# sceme1_0.net
KiCad netlist of a schematic drawn in EAGLE
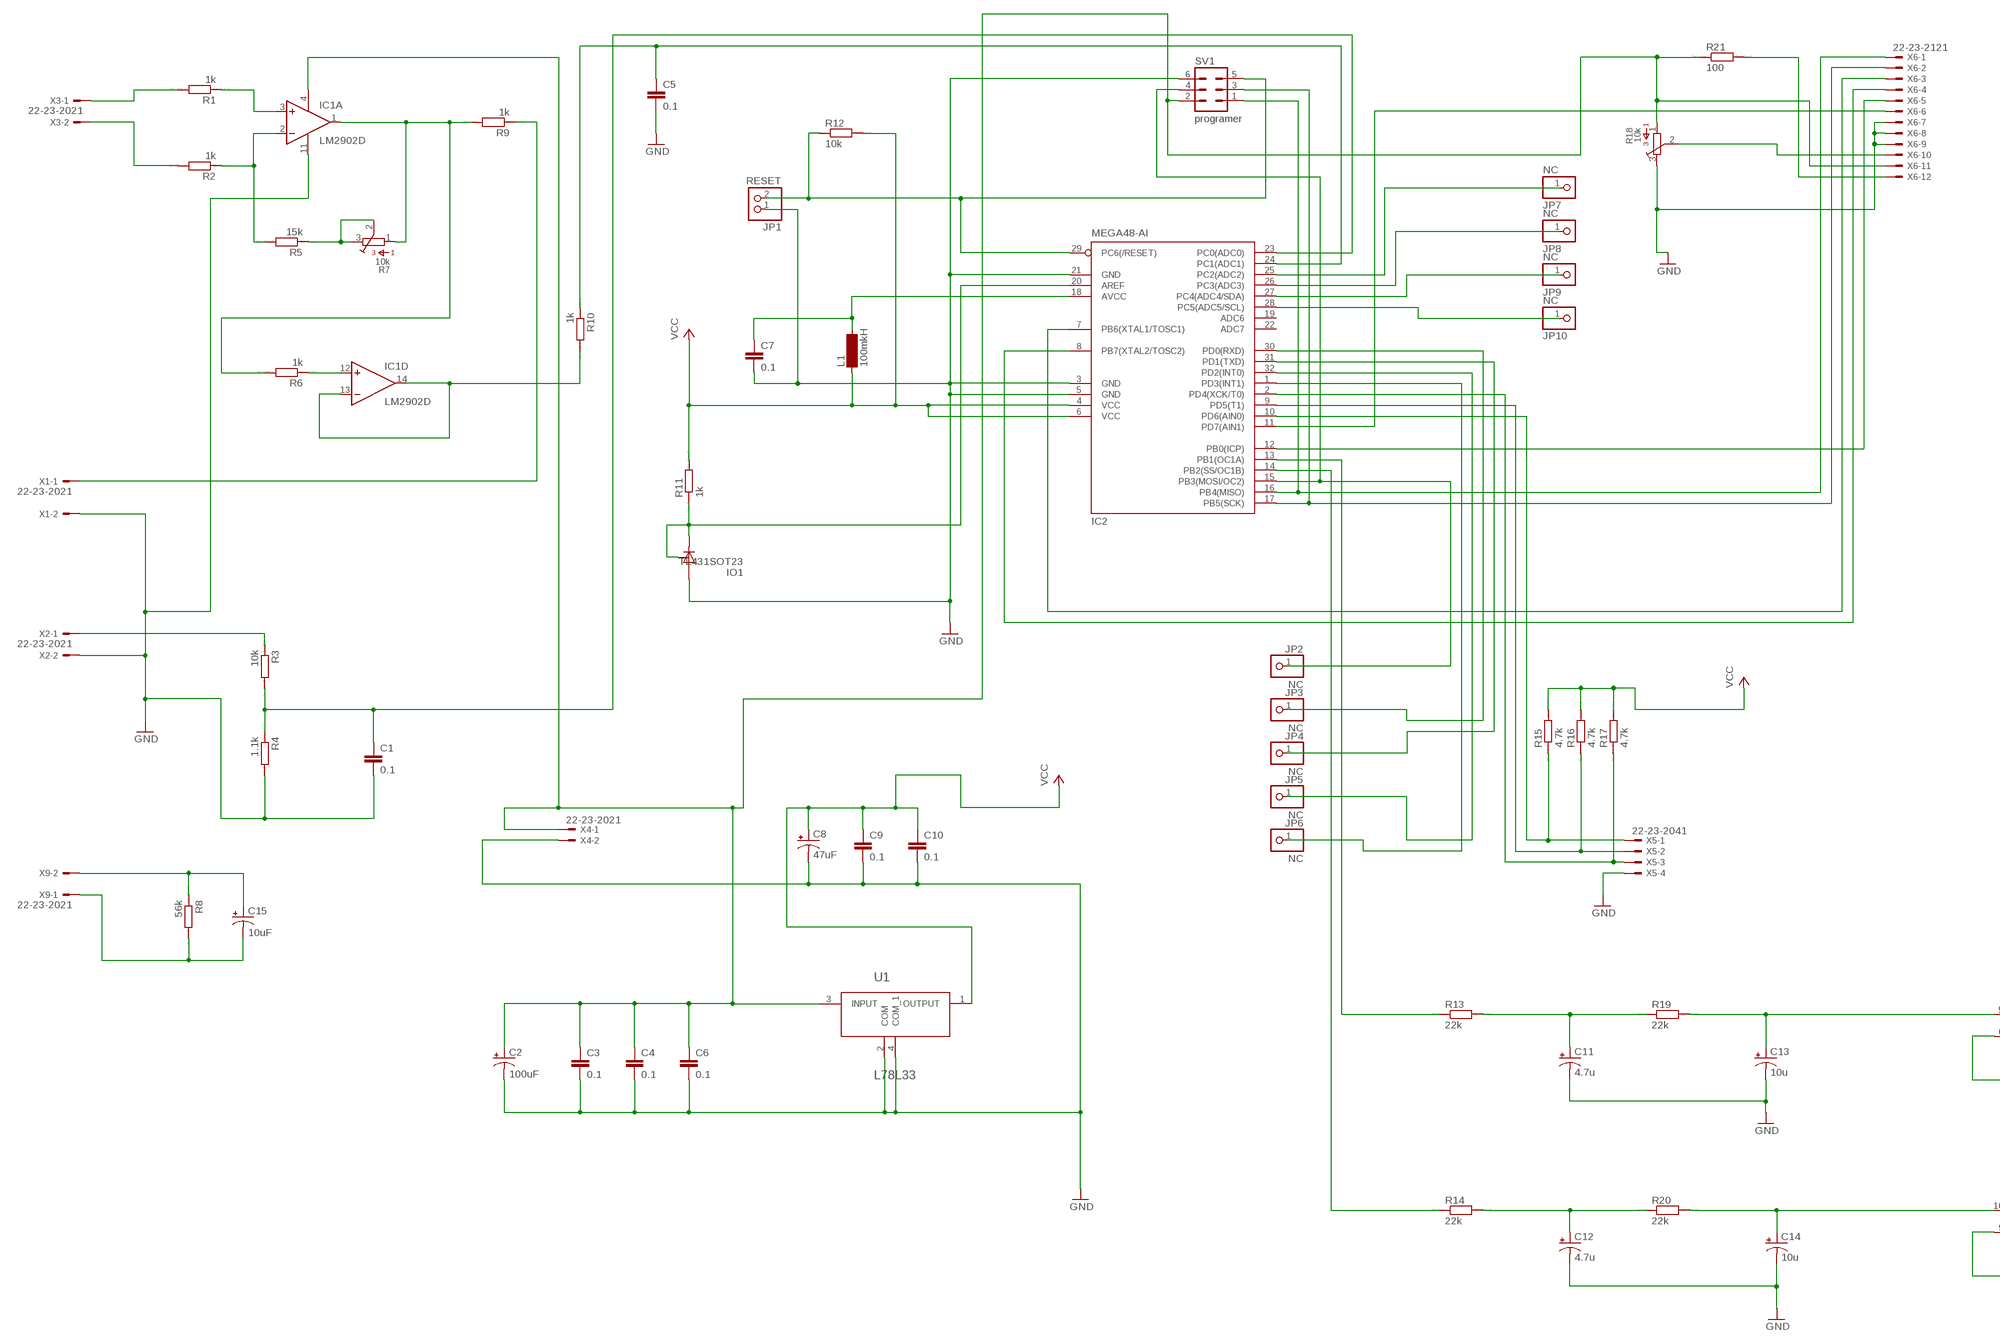
[diagram p0: schematic, sheet 1, part 1 of 2]
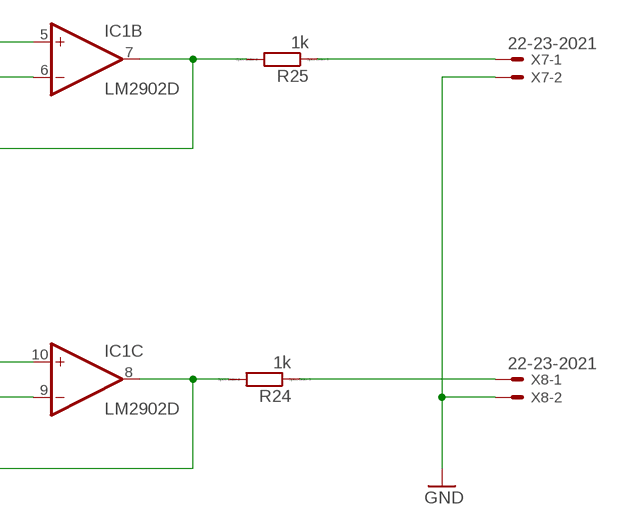
[diagram p1: schematic, sheet 1, part 2 of 2]

(export (version "E")
  (design (tool "Eeschema 10.0.6"))
  (components
    (comp (ref "C1")
      (value "0.1")
      (footprint "eagle-import:C0805")
      (libsource (lib "eagle-import") (part "C-EUC0805"))
    )
    (comp (ref "C2")
      (value "100uF")
      (footprint "eagle-import:E2,5-5")
      (libsource (lib "eagle-import") (part "CPOL-USE2.5-5"))
    )
    (comp (ref "C3")
      (value "0.1")
      (footprint "eagle-import:C0805")
      (libsource (lib "eagle-import") (part "C-EUC0805"))
    )
    (comp (ref "C4")
      (value "0.1")
      (footprint "eagle-import:C0805")
      (libsource (lib "eagle-import") (part "C-EUC0805"))
    )
    (comp (ref "C5")
      (value "0.1")
      (footprint "eagle-import:C0805")
      (libsource (lib "eagle-import") (part "C-EUC0805"))
    )
    (comp (ref "C6")
      (value "0.1")
      (footprint "eagle-import:C0805")
      (libsource (lib "eagle-import") (part "C-EUC0805"))
    )
    (comp (ref "C7")
      (value "0.1")
      (footprint "eagle-import:C0805")
      (libsource (lib "eagle-import") (part "C-EUC0805"))
    )
    (comp (ref "C8")
      (value "47uF")
      (footprint "eagle-import:E2,5-5")
      (libsource (lib "eagle-import") (part "CPOL-USE2.5-5"))
    )
    (comp (ref "C9")
      (value "0.1")
      (footprint "eagle-import:C0805")
      (libsource (lib "eagle-import") (part "C-EUC0805"))
    )
    (comp (ref "C10")
      (value "0.1")
      (footprint "eagle-import:C0805")
      (libsource (lib "eagle-import") (part "C-EUC0805"))
    )
    (comp (ref "C11")
      (value "4.7u")
      (footprint "eagle-import:E2,5-5")
      (libsource (lib "eagle-import") (part "CPOL-USE2.5-5"))
    )
    (comp (ref "C12")
      (value "4.7u")
      (footprint "eagle-import:E2,5-5")
      (libsource (lib "eagle-import") (part "CPOL-USE2.5-5"))
    )
    (comp (ref "C13")
      (value "10u")
      (footprint "eagle-import:E2,5-5")
      (libsource (lib "eagle-import") (part "CPOL-USE2.5-5"))
    )
    (comp (ref "C14")
      (value "10u")
      (footprint "eagle-import:E2,5-5")
      (libsource (lib "eagle-import") (part "CPOL-USE2.5-5"))
    )
    (comp (ref "C15")
      (value "10uF")
      (footprint "eagle-import:E2,5-5")
      (libsource (lib "eagle-import") (part "CPOL-USE2.5-5"))
    )
    (comp (ref "IC1")
      (value "LM2902D")
      (footprint "eagle-import:SO14")
      (libsource (lib "eagle-import") (part "LM2902D"))
    )
    (comp (ref "IC2")
      (value "MEGA48-AI")
      (footprint "eagle-import:TQFP32-08")
      (fields (field (name "MPN") "ATMEGA8-16AU"))
      (libsource (lib "eagle-import") (part "MEGA8-AI"))
    )
    (comp (ref "IO1")
      (value "TL431SOT23")
      (footprint "eagle-import:SOT23")
      (fields (field (name "MPN") "TL431BFDT"))
      (libsource (lib "eagle-import") (part "TL431SOT23"))
    )
    (comp (ref "JP1")
      (value "RESET")
      (footprint "eagle-import:1X02")
      (libsource (lib "eagle-import") (part "PINHD-1X2"))
    )
    (comp (ref "JP2")
      (value "NC")
      (footprint "eagle-import:1X01")
      (libsource (lib "eagle-import") (part "PINHD-1X1"))
    )
    (comp (ref "JP3")
      (value "NC")
      (footprint "eagle-import:1X01")
      (libsource (lib "eagle-import") (part "PINHD-1X1"))
    )
    (comp (ref "JP4")
      (value "NC")
      (footprint "eagle-import:1X01")
      (libsource (lib "eagle-import") (part "PINHD-1X1"))
    )
    (comp (ref "JP5")
      (value "NC")
      (footprint "eagle-import:1X01")
      (libsource (lib "eagle-import") (part "PINHD-1X1"))
    )
    (comp (ref "JP6")
      (value "NC")
      (footprint "eagle-import:1X01")
      (libsource (lib "eagle-import") (part "PINHD-1X1"))
    )
    (comp (ref "JP7")
      (value "NC")
      (footprint "eagle-import:1X01")
      (libsource (lib "eagle-import") (part "PINHD-1X1"))
    )
    (comp (ref "JP8")
      (value "NC")
      (footprint "eagle-import:1X01")
      (libsource (lib "eagle-import") (part "PINHD-1X1"))
    )
    (comp (ref "JP9")
      (value "NC")
      (footprint "eagle-import:1X01")
      (libsource (lib "eagle-import") (part "PINHD-1X1"))
    )
    (comp (ref "JP10")
      (value "NC")
      (footprint "eagle-import:1X01")
      (libsource (lib "eagle-import") (part "PINHD-1X1"))
    )
    (comp (ref "L1")
      (value "100mkH")
      (footprint "eagle-import:SM-1206")
      (libsource (lib "eagle-import") (part "SM-1206"))
    )
    (comp (ref "R1")
      (value "1k")
      (footprint "eagle-import:R0805")
      (libsource (lib "eagle-import") (part "R"))
    )
    (comp (ref "R2")
      (value "1k")
      (footprint "eagle-import:R0805")
      (libsource (lib "eagle-import") (part "R"))
    )
    (comp (ref "R3")
      (value "10k")
      (footprint "eagle-import:R0805")
      (libsource (lib "eagle-import") (part "R"))
    )
    (comp (ref "R4")
      (value "1.1k")
      (footprint "eagle-import:R0805")
      (libsource (lib "eagle-import") (part "R"))
    )
    (comp (ref "R5")
      (value "15k")
      (footprint "eagle-import:R0805")
      (libsource (lib "eagle-import") (part "R"))
    )
    (comp (ref "R6")
      (value "1k")
      (footprint "eagle-import:R0805")
      (libsource (lib "eagle-import") (part "R"))
    )
    (comp (ref "R7")
      (value "10k")
      (footprint "eagle-import:3362P")
      (libsource (lib "eagle-import") (part "3362P"))
    )
    (comp (ref "R8")
      (value "56k")
      (footprint "eagle-import:R0805")
      (libsource (lib "eagle-import") (part "R"))
    )
    (comp (ref "R9")
      (value "1k")
      (footprint "eagle-import:R0805")
      (libsource (lib "eagle-import") (part "R"))
    )
    (comp (ref "R10")
      (value "1k")
      (footprint "eagle-import:R0805")
      (libsource (lib "eagle-import") (part "R"))
    )
    (comp (ref "R11")
      (value "1k")
      (footprint "eagle-import:R0805")
      (libsource (lib "eagle-import") (part "R"))
    )
    (comp (ref "R12")
      (value "10k")
      (footprint "eagle-import:R0805")
      (libsource (lib "eagle-import") (part "R"))
    )
    (comp (ref "R13")
      (value "22k")
      (footprint "eagle-import:R0805")
      (libsource (lib "eagle-import") (part "R"))
    )
    (comp (ref "R14")
      (value "22k")
      (footprint "eagle-import:R0805")
      (libsource (lib "eagle-import") (part "R"))
    )
    (comp (ref "R15")
      (value "4.7k")
      (footprint "eagle-import:R0805")
      (libsource (lib "eagle-import") (part "R"))
    )
    (comp (ref "R16")
      (value "4.7k")
      (footprint "eagle-import:R0805")
      (libsource (lib "eagle-import") (part "R"))
    )
    (comp (ref "R17")
      (value "4.7k")
      (footprint "eagle-import:R0805")
      (libsource (lib "eagle-import") (part "R"))
    )
    (comp (ref "R18")
      (value "10k")
      (footprint "eagle-import:3362P")
      (libsource (lib "eagle-import") (part "3362P"))
    )
    (comp (ref "R19")
      (value "22k")
      (footprint "eagle-import:R0805")
      (libsource (lib "eagle-import") (part "R"))
    )
    (comp (ref "R20")
      (value "22k")
      (footprint "eagle-import:R0805")
      (libsource (lib "eagle-import") (part "R"))
    )
    (comp (ref "R21")
      (value "100")
      (footprint "eagle-import:R0805")
      (libsource (lib "eagle-import") (part "R"))
    )
    (comp (ref "R24")
      (value "1k")
      (footprint "eagle-import:R0805")
      (libsource (lib "eagle-import") (part "R"))
    )
    (comp (ref "R25")
      (value "1k")
      (footprint "eagle-import:R0805")
      (libsource (lib "eagle-import") (part "R"))
    )
    (comp (ref "SV1")
      (value "programer")
      (footprint "eagle-import:ML6")
      (libsource (lib "eagle-import") (part "ML6"))
    )
    (comp (ref "U1")
      (value "L78L33")
      (footprint "eagle-import:SOT150P400X160-4N")
      (fields (field (name "MPN") "UA78L05CPK"))
      (libsource (lib "eagle-import") (part "UA78L05CPK"))
    )
    (comp (ref "X1")
      (value "22-23-2021")
      (footprint "eagle-import:22-23-2021")
      (fields (field (name "MF") "MOLEX"))
      (libsource (lib "eagle-import") (part "22-23-2021"))
    )
    (comp (ref "X2")
      (value "22-23-2021")
      (footprint "eagle-import:22-23-2021")
      (fields (field (name "MF") "MOLEX"))
      (libsource (lib "eagle-import") (part "22-23-2021"))
    )
    (comp (ref "X3")
      (value "22-23-2021")
      (footprint "eagle-import:22-23-2021")
      (fields (field (name "MF") "MOLEX"))
      (libsource (lib "eagle-import") (part "22-23-2021"))
    )
    (comp (ref "X4")
      (value "22-23-2021")
      (footprint "eagle-import:22-23-2021")
      (fields (field (name "MF") "MOLEX"))
      (libsource (lib "eagle-import") (part "22-23-2021"))
    )
    (comp (ref "X5")
      (value "22-23-2041")
      (footprint "eagle-import:22-23-2041")
      (fields (field (name "MF") "MOLEX"))
      (libsource (lib "eagle-import") (part "22-23-2041"))
    )
    (comp (ref "X6")
      (value "22-23-2121")
      (footprint "eagle-import:22-23-2121")
      (fields (field (name "MF") "MOLEX"))
      (libsource (lib "eagle-import") (part "22-23-2121"))
    )
    (comp (ref "X7")
      (value "22-23-2021")
      (footprint "eagle-import:22-23-2021")
      (fields (field (name "MF") "MOLEX"))
      (libsource (lib "eagle-import") (part "22-23-2021"))
    )
    (comp (ref "X8")
      (value "22-23-2021")
      (footprint "eagle-import:22-23-2021")
      (fields (field (name "MF") "MOLEX"))
      (libsource (lib "eagle-import") (part "22-23-2021"))
    )
    (comp (ref "X9")
      (value "22-23-2021")
      (footprint "eagle-import:22-23-2021")
      (fields (field (name "MF") "MOLEX"))
      (libsource (lib "eagle-import") (part "22-23-2021"))
    )
  )
  (nets
    (net (code "1") (name "GND") (class "Default")
      (node (ref "C1") (pin "2") (pinfunction "2_2") (pintype "passive"))
      (node (ref "C10") (pin "2") (pinfunction "2_2") (pintype "passive"))
      (node (ref "C11") (pin "-") (pinfunction "-_-") (pintype "passive"))
      (node (ref "C12") (pin "-") (pinfunction "-_-") (pintype "passive"))
      (node (ref "C13") (pin "-") (pinfunction "-_-") (pintype "passive"))
      (node (ref "C14") (pin "-") (pinfunction "-_-") (pintype "passive"))
      (node (ref "C2") (pin "-") (pinfunction "-_-") (pintype "passive"))
      (node (ref "C3") (pin "2") (pinfunction "2_2") (pintype "passive"))
      (node (ref "C4") (pin "2") (pinfunction "2_2") (pintype "passive"))
      (node (ref "C5") (pin "2") (pinfunction "2_2") (pintype "passive"))
      (node (ref "C6") (pin "2") (pinfunction "2_2") (pintype "passive"))
      (node (ref "C7") (pin "2") (pinfunction "2_2") (pintype "passive"))
      (node (ref "C8") (pin "-") (pinfunction "-_-") (pintype "passive"))
      (node (ref "C9") (pin "2") (pinfunction "2_2") (pintype "passive"))
      (node (ref "IC1") (pin "11") (pinfunction "V-_11") (pintype "power_in"))
      (node (ref "IC2") (pin "21") (pinfunction "GND_21") (pintype "power_in"))
      (node (ref "IC2") (pin "3") (pinfunction "GND_3") (pintype "power_in"))
      (node (ref "IC2") (pin "5") (pinfunction "GND_5") (pintype "power_in"))
      (node (ref "IO1") (pin "3") (pinfunction "A_3") (pintype "bidirectional"))
      (node (ref "JP1") (pin "1") (pinfunction "1_1") (pintype "passive"))
      (node (ref "R18") (pin "3") (pinfunction "3_3") (pintype "passive"))
      (node (ref "R4") (pin "2") (pinfunction "2_2") (pintype "passive"))
      (node (ref "SV1") (pin "6") (pinfunction "6_6") (pintype "passive"))
      (node (ref "U1") (pin "2") (pinfunction "COM_2") (pintype "power_in"))
      (node (ref "U1") (pin "4") (pinfunction "COM_1_4") (pintype "power_in"))
      (node (ref "X1") (pin "2") (pinfunction "S_2") (pintype "passive"))
      (node (ref "X2") (pin "2") (pinfunction "S_2") (pintype "passive"))
      (node (ref "X4") (pin "2") (pinfunction "S_2") (pintype "passive"))
      (node (ref "X5") (pin "4") (pinfunction "S_4") (pintype "passive"))
      (node (ref "X6") (pin "7") (pinfunction "S_7") (pintype "passive"))
      (node (ref "X6") (pin "8") (pinfunction "S_8") (pintype "passive"))
      (node (ref "X6") (pin "9") (pinfunction "S_9") (pintype "passive"))
      (node (ref "X7") (pin "2") (pinfunction "S_2") (pintype "passive"))
      (node (ref "X8") (pin "2") (pinfunction "S_2") (pintype "passive"))
    )
    (net (code "2") (name "Net-(C11-Pad+)") (class "Default")
      (node (ref "C11") (pin "+") (pinfunction "+_+") (pintype "passive"))
      (node (ref "R13") (pin "2") (pinfunction "2_2") (pintype "passive"))
      (node (ref "R19") (pin "1") (pinfunction "1_1") (pintype "passive"))
    )
    (net (code "3") (name "Net-(C12-Pad+)") (class "Default")
      (node (ref "C12") (pin "+") (pinfunction "+_+") (pintype "passive"))
      (node (ref "R14") (pin "2") (pinfunction "2_2") (pintype "passive"))
      (node (ref "R20") (pin "1") (pinfunction "1_1") (pintype "passive"))
    )
    (net (code "4") (name "Net-(IC1A-+IN)") (class "Default")
      (node (ref "IC1") (pin "3") (pinfunction "+IN_3") (pintype "input"))
      (node (ref "R1") (pin "1") (pinfunction "1_1") (pintype "passive"))
    )
    (net (code "5") (name "Net-(IC1A--IN)") (class "Default")
      (node (ref "IC1") (pin "2") (pinfunction "-IN_2") (pintype "input"))
      (node (ref "R2") (pin "1") (pinfunction "1_1") (pintype "passive"))
      (node (ref "R5") (pin "2") (pinfunction "2_2") (pintype "passive"))
    )
    (net (code "6") (name "Net-(IC1A-OUT)") (class "Default")
      (node (ref "IC1") (pin "1") (pinfunction "OUT_1") (pintype "output"))
      (node (ref "R6") (pin "2") (pinfunction "2_2") (pintype "passive"))
      (node (ref "R7") (pin "1") (pinfunction "1_1") (pintype "passive"))
      (node (ref "R9") (pin "2") (pinfunction "2_2") (pintype "passive"))
    )
    (net (code "7") (name "Net-(IC1B-+IN)") (class "Default")
      (node (ref "C13") (pin "+") (pinfunction "+_+") (pintype "passive"))
      (node (ref "IC1") (pin "5") (pinfunction "+IN_5") (pintype "input"))
      (node (ref "R19") (pin "2") (pinfunction "2_2") (pintype "passive"))
    )
    (net (code "8") (name "Net-(IC1B--IN)") (class "Default")
      (node (ref "IC1") (pin "6") (pinfunction "-IN_6") (pintype "input"))
      (node (ref "IC1") (pin "7") (pinfunction "OUT_7") (pintype "output"))
      (node (ref "R25") (pin "2") (pinfunction "2_2") (pintype "passive"))
    )
    (net (code "9") (name "Net-(IC1C-+IN)") (class "Default")
      (node (ref "C14") (pin "+") (pinfunction "+_+") (pintype "passive"))
      (node (ref "IC1") (pin "10") (pinfunction "+IN_10") (pintype "input"))
      (node (ref "R20") (pin "2") (pinfunction "2_2") (pintype "passive"))
    )
    (net (code "10") (name "Net-(IC1C--IN)") (class "Default")
      (node (ref "IC1") (pin "8") (pinfunction "OUT_8") (pintype "output"))
      (node (ref "IC1") (pin "9") (pinfunction "-IN_9") (pintype "input"))
      (node (ref "R24") (pin "2") (pinfunction "2_2") (pintype "passive"))
    )
    (net (code "11") (name "Net-(IC1D-+IN)") (class "Default")
      (node (ref "IC1") (pin "12") (pinfunction "+IN_12") (pintype "input"))
      (node (ref "R6") (pin "1") (pinfunction "1_1") (pintype "passive"))
    )
    (net (code "12") (name "Net-(IC1D--IN)") (class "Default")
      (node (ref "IC1") (pin "13") (pinfunction "-IN_13") (pintype "input"))
      (node (ref "IC1") (pin "14") (pinfunction "OUT_14") (pintype "output"))
      (node (ref "R10") (pin "2") (pinfunction "2_2") (pintype "passive"))
    )
    (net (code "13") (name "Net-(IC1E-V+)") (class "Default")
      (node (ref "C2") (pin "+") (pinfunction "+_+") (pintype "passive"))
      (node (ref "C3") (pin "1") (pinfunction "1_1") (pintype "passive"))
      (node (ref "C4") (pin "1") (pinfunction "1_1") (pintype "passive"))
      (node (ref "C6") (pin "1") (pinfunction "1_1") (pintype "passive"))
      (node (ref "IC1") (pin "4") (pinfunction "V+_4") (pintype "power_in"))
      (node (ref "R18") (pin "1") (pinfunction "1_1") (pintype "passive"))
      (node (ref "R21") (pin "1") (pinfunction "1_1") (pintype "passive"))
      (node (ref "SV1") (pin "2") (pinfunction "2_2") (pintype "passive"))
      (node (ref "U1") (pin "3") (pinfunction "INPUT_3") (pintype "input"))
      (node (ref "X4") (pin "1") (pinfunction "S_1") (pintype "passive"))
      (node (ref "X6") (pin "11") (pinfunction "S_11") (pintype "passive"))
    )
    (net (code "14") (name "Net-(IC2-AREF)") (class "Default")
      (node (ref "IC2") (pin "20") (pinfunction "AREF_20") (pintype "passive"))
      (node (ref "IO1") (pin "1") (pinfunction "C_1") (pintype "bidirectional"))
      (node (ref "IO1") (pin "2") (pinfunction "R_2") (pintype "bidirectional"))
      (node (ref "R11") (pin "1") (pinfunction "1_1") (pintype "passive"))
    )
    (net (code "15") (name "Net-(IC2-AVCC)") (class "Default")
      (node (ref "C7") (pin "1") (pinfunction "1_1") (pintype "passive"))
      (node (ref "IC2") (pin "18") (pinfunction "AVCC_18") (pintype "power_in"))
      (node (ref "L1") (pin "2") (pinfunction "2_2") (pintype "passive"))
    )
    (net (code "16") (name "Net-(IC2-PB0(ICP))") (class "Default")
      (node (ref "IC2") (pin "12") (pinfunction "PB0(ICP)_12") (pintype "bidirectional"))
      (node (ref "X6") (pin "5") (pinfunction "S_5") (pintype "passive"))
    )
    (net (code "17") (name "Net-(IC2-PB1(OC1A))") (class "Default")
      (node (ref "IC2") (pin "13") (pinfunction "PB1(OC1A)_13") (pintype "bidirectional"))
      (node (ref "R13") (pin "1") (pinfunction "1_1") (pintype "passive"))
    )
    (net (code "18") (name "Net-(IC2-PB2(SS{slash}OC1B))") (class "Default")
      (node (ref "IC2") (pin "14") (pinfunction "PB2(SS/OC1B)_14") (pintype "bidirectional"))
      (node (ref "R14") (pin "1") (pinfunction "1_1") (pintype "passive"))
    )
    (net (code "19") (name "Net-(IC2-PB3(MOSI{slash}OC2))") (class "Default")
      (node (ref "IC2") (pin "15") (pinfunction "PB3(MOSI/OC2)_15") (pintype "bidirectional"))
      (node (ref "JP2") (pin "1") (pinfunction "1_1") (pintype "passive"))
      (node (ref "SV1") (pin "4") (pinfunction "4_4") (pintype "passive"))
    )
    (net (code "20") (name "Net-(IC2-PB4(MISO))") (class "Default")
      (node (ref "IC2") (pin "16") (pinfunction "PB4(MISO)_16") (pintype "bidirectional"))
      (node (ref "SV1") (pin "1") (pinfunction "1_1") (pintype "passive"))
      (node (ref "X6") (pin "1") (pinfunction "S_1") (pintype "passive"))
    )
    (net (code "21") (name "Net-(IC2-PB5(SCK))") (class "Default")
      (node (ref "IC2") (pin "17") (pinfunction "PB5(SCK)_17") (pintype "bidirectional"))
      (node (ref "SV1") (pin "3") (pinfunction "3_3") (pintype "passive"))
      (node (ref "X6") (pin "2") (pinfunction "S_2") (pintype "passive"))
    )
    (net (code "22") (name "Net-(IC2-PB6(XTAL1{slash}TOSC1))") (class "Default")
      (node (ref "IC2") (pin "7") (pinfunction "PB6(XTAL1/TOSC1)_7") (pintype "bidirectional"))
      (node (ref "X6") (pin "3") (pinfunction "S_3") (pintype "passive"))
    )
    (net (code "23") (name "Net-(IC2-PB7(XTAL2{slash}TOSC2))") (class "Default")
      (node (ref "IC2") (pin "8") (pinfunction "PB7(XTAL2/TOSC2)_8") (pintype "bidirectional"))
      (node (ref "X6") (pin "4") (pinfunction "S_4") (pintype "passive"))
    )
    (net (code "24") (name "Net-(IC2-PC0(ADC0))") (class "Default")
      (node (ref "C1") (pin "1") (pinfunction "1_1") (pintype "passive"))
      (node (ref "IC2") (pin "23") (pinfunction "PC0(ADC0)_23") (pintype "bidirectional"))
      (node (ref "R3") (pin "2") (pinfunction "2_2") (pintype "passive"))
      (node (ref "R4") (pin "1") (pinfunction "1_1") (pintype "passive"))
    )
    (net (code "25") (name "Net-(IC2-PC1(ADC1))") (class "Default")
      (node (ref "C5") (pin "1") (pinfunction "1_1") (pintype "passive"))
      (node (ref "IC2") (pin "24") (pinfunction "PC1(ADC1)_24") (pintype "bidirectional"))
      (node (ref "R10") (pin "1") (pinfunction "1_1") (pintype "passive"))
    )
    (net (code "26") (name "Net-(IC2-PC2(ADC2))") (class "Default")
      (node (ref "IC2") (pin "25") (pinfunction "PC2(ADC2)_25") (pintype "bidirectional"))
      (node (ref "JP7") (pin "1") (pinfunction "1_1") (pintype "passive"))
    )
    (net (code "27") (name "Net-(IC2-PC3(ADC3))") (class "Default")
      (node (ref "IC2") (pin "26") (pinfunction "PC3(ADC3)_26") (pintype "bidirectional"))
      (node (ref "JP8") (pin "1") (pinfunction "1_1") (pintype "passive"))
    )
    (net (code "28") (name "Net-(IC2-PC4(ADC4{slash}SDA))") (class "Default")
      (node (ref "IC2") (pin "27") (pinfunction "PC4(ADC4/SDA)_27") (pintype "bidirectional"))
      (node (ref "JP9") (pin "1") (pinfunction "1_1") (pintype "passive"))
    )
    (net (code "29") (name "Net-(IC2-PC5(ADC5{slash}SCL))") (class "Default")
      (node (ref "IC2") (pin "28") (pinfunction "PC5(ADC5/SCL)_28") (pintype "bidirectional"))
      (node (ref "JP10") (pin "1") (pinfunction "1_1") (pintype "passive"))
    )
    (net (code "30") (name "Net-(IC2-PC6({slash}RESET))") (class "Default")
      (node (ref "IC2") (pin "29") (pinfunction "PC6(/RESET)_29") (pintype "bidirectional"))
      (node (ref "JP1") (pin "2") (pinfunction "2_2") (pintype "passive"))
      (node (ref "R12") (pin "1") (pinfunction "1_1") (pintype "passive"))
      (node (ref "SV1") (pin "5") (pinfunction "5_5") (pintype "passive"))
    )
    (net (code "31") (name "Net-(IC2-PD0(RXD))") (class "Default")
      (node (ref "IC2") (pin "30") (pinfunction "PD0(RXD)_30") (pintype "bidirectional"))
      (node (ref "JP3") (pin "1") (pinfunction "1_1") (pintype "passive"))
    )
    (net (code "32") (name "Net-(IC2-PD1(TXD))") (class "Default")
      (node (ref "IC2") (pin "31") (pinfunction "PD1(TXD)_31") (pintype "bidirectional"))
      (node (ref "JP4") (pin "1") (pinfunction "1_1") (pintype "passive"))
    )
    (net (code "33") (name "Net-(IC2-PD2(INT0))") (class "Default")
      (node (ref "IC2") (pin "32") (pinfunction "PD2(INT0)_32") (pintype "bidirectional"))
      (node (ref "JP5") (pin "1") (pinfunction "1_1") (pintype "passive"))
    )
    (net (code "34") (name "Net-(IC2-PD3(INT1))") (class "Default")
      (node (ref "IC2") (pin "1") (pinfunction "PD3(INT1)_1") (pintype "bidirectional"))
      (node (ref "JP6") (pin "1") (pinfunction "1_1") (pintype "passive"))
    )
    (net (code "35") (name "Net-(IC2-PD4(XCK{slash}T0))") (class "Default")
      (node (ref "IC2") (pin "2") (pinfunction "PD4(XCK/T0)_2") (pintype "bidirectional"))
      (node (ref "R17") (pin "1") (pinfunction "1_1") (pintype "passive"))
      (node (ref "X5") (pin "3") (pinfunction "S_3") (pintype "passive"))
    )
    (net (code "36") (name "Net-(IC2-PD5(T1))") (class "Default")
      (node (ref "IC2") (pin "9") (pinfunction "PD5(T1)_9") (pintype "bidirectional"))
      (node (ref "R16") (pin "1") (pinfunction "1_1") (pintype "passive"))
      (node (ref "X5") (pin "2") (pinfunction "S_2") (pintype "passive"))
    )
    (net (code "37") (name "Net-(IC2-PD6(AIN0))") (class "Default")
      (node (ref "IC2") (pin "10") (pinfunction "PD6(AIN0)_10") (pintype "bidirectional"))
      (node (ref "R15") (pin "1") (pinfunction "1_1") (pintype "passive"))
      (node (ref "X5") (pin "1") (pinfunction "S_1") (pintype "passive"))
    )
    (net (code "38") (name "Net-(IC2-PD7(AIN1))") (class "Default")
      (node (ref "IC2") (pin "11") (pinfunction "PD7(AIN1)_11") (pintype "bidirectional"))
      (node (ref "X6") (pin "6") (pinfunction "S_6") (pintype "passive"))
    )
    (net (code "39") (name "Net-(R5-Pad1)") (class "Default")
      (node (ref "R5") (pin "1") (pinfunction "1_1") (pintype "passive"))
      (node (ref "R7") (pin "2") (pinfunction "2_2") (pintype "passive"))
      (node (ref "R7") (pin "3") (pinfunction "3_3") (pintype "passive"))
    )
    (net (code "40") (name "Net-(X1A-S)") (class "Default")
      (node (ref "R9") (pin "1") (pinfunction "1_1") (pintype "passive"))
      (node (ref "X1") (pin "1") (pinfunction "S_1") (pintype "passive"))
    )
    (net (code "41") (name "Net-(X2A-S)") (class "Default")
      (node (ref "R3") (pin "1") (pinfunction "1_1") (pintype "passive"))
      (node (ref "X2") (pin "1") (pinfunction "S_1") (pintype "passive"))
    )
    (net (code "42") (name "Net-(X3A-S)") (class "Default")
      (node (ref "R1") (pin "2") (pinfunction "2_2") (pintype "passive"))
      (node (ref "X3") (pin "1") (pinfunction "S_1") (pintype "passive"))
    )
    (net (code "43") (name "Net-(X3B-S)") (class "Default")
      (node (ref "R2") (pin "2") (pinfunction "2_2") (pintype "passive"))
      (node (ref "X3") (pin "2") (pinfunction "S_2") (pintype "passive"))
    )
    (net (code "44") (name "Net-(X6B-S)") (class "Default")
      (node (ref "R18") (pin "2") (pinfunction "2_2") (pintype "passive"))
      (node (ref "X6") (pin "10") (pinfunction "S_10") (pintype "passive"))
    )
    (net (code "45") (name "Net-(X6D-S)") (class "Default")
      (node (ref "R21") (pin "2") (pinfunction "2_2") (pintype "passive"))
      (node (ref "X6") (pin "12") (pinfunction "S_12") (pintype "passive"))
    )
    (net (code "46") (name "Net-(X7A-S)") (class "Default")
      (node (ref "R25") (pin "1") (pinfunction "1_1") (pintype "passive"))
      (node (ref "X7") (pin "1") (pinfunction "S_1") (pintype "passive"))
    )
    (net (code "47") (name "Net-(X8A-S)") (class "Default")
      (node (ref "R24") (pin "1") (pinfunction "1_1") (pintype "passive"))
      (node (ref "X8") (pin "1") (pinfunction "S_1") (pintype "passive"))
    )
    (net (code "48") (name "Net-(X9A-S)") (class "Default")
      (node (ref "C15") (pin "-") (pinfunction "-_-") (pintype "passive"))
      (node (ref "R8") (pin "2") (pinfunction "2_2") (pintype "passive"))
      (node (ref "X9") (pin "1") (pinfunction "S_1") (pintype "passive"))
    )
    (net (code "49") (name "Net-(X9B-S)") (class "Default")
      (node (ref "C15") (pin "+") (pinfunction "+_+") (pintype "passive"))
      (node (ref "R8") (pin "1") (pinfunction "1_1") (pintype "passive"))
      (node (ref "X9") (pin "2") (pinfunction "S_2") (pintype "passive"))
    )
    (net (code "50") (name "VCC") (class "Default")
      (node (ref "C10") (pin "1") (pinfunction "1_1") (pintype "passive"))
      (node (ref "C8") (pin "+") (pinfunction "+_+") (pintype "passive"))
      (node (ref "C9") (pin "1") (pinfunction "1_1") (pintype "passive"))
      (node (ref "IC2") (pin "4") (pinfunction "VCC_4") (pintype "power_in"))
      (node (ref "IC2") (pin "6") (pinfunction "VCC_6") (pintype "power_in"))
      (node (ref "L1") (pin "1") (pinfunction "1_1") (pintype "passive"))
      (node (ref "R11") (pin "2") (pinfunction "2_2") (pintype "passive"))
      (node (ref "R12") (pin "2") (pinfunction "2_2") (pintype "passive"))
      (node (ref "R15") (pin "2") (pinfunction "2_2") (pintype "passive"))
      (node (ref "R16") (pin "2") (pinfunction "2_2") (pintype "passive"))
      (node (ref "R17") (pin "2") (pinfunction "2_2") (pintype "passive"))
      (node (ref "U1") (pin "1") (pinfunction "OUTPUT_1") (pintype "output"))
    )
    (net (code "51") (name "unconnected-(IC2-ADC6-Pad19)") (class "Default")
      (node (ref "IC2") (pin "19") (pinfunction "ADC6_19") (pintype "bidirectional"))
    )
    (net (code "52") (name "unconnected-(IC2-ADC7-Pad22)") (class "Default")
      (node (ref "IC2") (pin "22") (pinfunction "ADC7_22") (pintype "bidirectional"))
    )
  )
)
